# Dual_5V_3_3V_Switch_Mode_PSU.net
KiCad netlist of a schematic drawn in Altium Designer
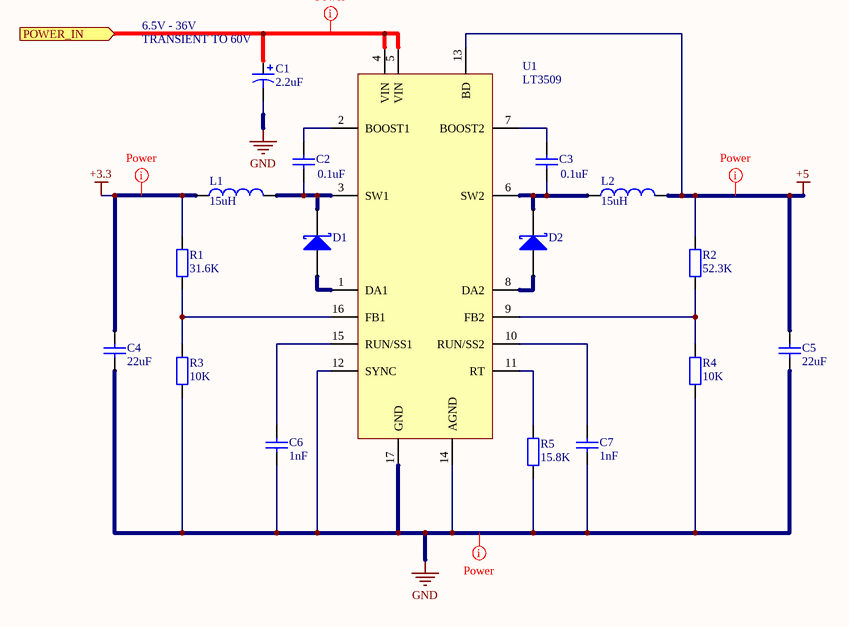
[diagram p0: Dual 5V+3.3V Switch Mode PSU.SchDoc]

(export (version "E")
  (design (tool "Eeschema 10.0.6"))
  (components
    (comp (ref "C1")
      (value "2.2uF")
      (footprint "EEEHC1H2R2R")
      (description "Polarized Capacitor (Radial)")
      (fields (field (name "Comment") "Cap Pol1") (field (name "PUBLISHER") "Altium Limited"))
      (libsource (lib "Miscellaneous Devices") (part "Cap Pol1"))
    )
    (comp (ref "C2")
      (value "0.1uF")
      (footprint "C0603")
      (description "Capacitor")
      (fields (field (name "Comment") "Cap") (field (name "PUBLISHER") "Altium Limited"))
      (libsource (lib "Miscellaneous Devices") (part "Cap"))
    )
    (comp (ref "C3")
      (value "0.1uF")
      (footprint "C0603")
      (description "Capacitor")
      (fields (field (name "Comment") "Cap") (field (name "PUBLISHER") "Altium Limited"))
      (libsource (lib "Miscellaneous Devices") (part "Cap"))
    )
    (comp (ref "C4")
      (value "22uF")
      (footprint "C0805")
      (description "Capacitor")
      (fields (field (name "Comment") "Cap"))
      (libsource (lib "Miscellaneous Devices") (part "Cap"))
    )
    (comp (ref "C5")
      (value "22uF")
      (footprint "C0805")
      (description "Capacitor")
      (fields (field (name "Comment") "Cap"))
      (libsource (lib "Miscellaneous Devices") (part "Cap"))
    )
    (comp (ref "C6")
      (value "1nF")
      (footprint "C0603")
      (description "Capacitor")
      (fields (field (name "Comment") "Cap"))
      (libsource (lib "Miscellaneous Devices") (part "Cap"))
    )
    (comp (ref "C7")
      (value "1nF")
      (footprint "C0603")
      (description "Capacitor")
      (fields (field (name "Comment") "Cap"))
      (libsource (lib "Miscellaneous Devices") (part "Cap"))
    )
    (comp (ref "D1")
      (value "D Schottky")
      (footprint "VS-10BQ030TRPBF")
      (description "Schottky Diode")
      (fields (field (name "PUBLISHER") "Altium Limited"))
      (libsource (lib "Miscellaneous Devices") (part "D Schottky"))
    )
    (comp (ref "D2")
      (value "D Schottky")
      (footprint "VS-10BQ030TRPBF")
      (description "Schottky Diode")
      (fields (field (name "PUBLISHER") "Altium Limited"))
      (libsource (lib "Miscellaneous Devices") (part "D Schottky"))
    )
    (comp (ref "L1")
      (value "15uH")
      (footprint "SDR0604-150YL")
      (description "Inductor")
      (fields (field (name "PUBLISHER") "Altium Limited"))
      (libsource (lib "Miscellaneous Devices") (part "Inductor"))
    )
    (comp (ref "L2")
      (value "15uH")
      (footprint "SDR0604-150YL")
      (description "Inductor")
      (fields (field (name "PUBLISHER") "Altium Limited"))
      (libsource (lib "Miscellaneous Devices") (part "Inductor"))
    )
    (comp (ref "R1")
      (value "31.6K")
      (footprint "R0603")
      (description "Resistor")
      (fields (field (name "Comment") "Res"))
      (libsource (lib "Miscellaneous Devices") (part "Res2"))
    )
    (comp (ref "R2")
      (value "52.3K")
      (footprint "R0603")
      (description "Resistor")
      (fields (field (name "Comment") "Res"))
      (libsource (lib "Miscellaneous Devices") (part "Res2"))
    )
    (comp (ref "R3")
      (value "10K")
      (footprint "R0603")
      (description "Resistor")
      (fields (field (name "Comment") "Res"))
      (libsource (lib "Miscellaneous Devices") (part "Res2"))
    )
    (comp (ref "R4")
      (value "10K")
      (footprint "R0603")
      (description "Resistor")
      (fields (field (name "Comment") "Res"))
      (libsource (lib "Miscellaneous Devices") (part "Res2"))
    )
    (comp (ref "R5")
      (value "15.8K")
      (footprint "R0603")
      (description "Resistor")
      (fields (field (name "Comment") "Res"))
      (libsource (lib "Miscellaneous Devices") (part "Res2"))
    )
    (comp (ref "U1") (value "LT3509") (footprint "LT3509") (libsource (lib "LT3509") (part "LT3509")))
  )
  (nets
    (net (code "1") (name "+3.3") (class "Default")
      (node (ref "C4") (pin "1") (pinfunction "1_1") (pintype "passive"))
      (node (ref "L1") (pin "1") (pinfunction "1_1") (pintype "passive"))
      (node (ref "R1") (pin "2") (pinfunction "2_2") (pintype "passive"))
    )
    (net (code "2") (name "+5") (class "Default")
      (node (ref "C5") (pin "1") (pinfunction "1_1") (pintype "passive"))
      (node (ref "L2") (pin "2") (pinfunction "2_2") (pintype "passive"))
      (node (ref "R2") (pin "2") (pinfunction "2_2") (pintype "passive"))
      (node (ref "U1") (pin "13") (pinfunction "BD_13") (pintype "passive"))
    )
    (net (code "3") (name "/POWER_IN") (class "Default")
      (node (ref "C1") (pin "1") (pinfunction "1_1") (pintype "passive"))
      (node (ref "U1") (pin "4") (pinfunction "VIN_4") (pintype "passive"))
      (node (ref "U1") (pin "5") (pinfunction "VIN_5") (pintype "passive"))
    )
    (net (code "4") (name "GND") (class "Default")
      (node (ref "C1") (pin "2") (pinfunction "2_2") (pintype "passive"))
      (node (ref "C4") (pin "2") (pinfunction "2_2") (pintype "passive"))
      (node (ref "C5") (pin "2") (pinfunction "2_2") (pintype "passive"))
      (node (ref "C6") (pin "2") (pinfunction "2_2") (pintype "passive"))
      (node (ref "C7") (pin "2") (pinfunction "2_2") (pintype "passive"))
      (node (ref "R3") (pin "1") (pinfunction "1_1") (pintype "passive"))
      (node (ref "R4") (pin "1") (pinfunction "1_1") (pintype "passive"))
      (node (ref "R5") (pin "1") (pinfunction "1_1") (pintype "passive"))
      (node (ref "U1") (pin "12") (pinfunction "SYNC_12") (pintype "passive"))
      (node (ref "U1") (pin "14") (pinfunction "AGND_14") (pintype "power_in"))
      (node (ref "U1") (pin "17") (pinfunction "GND_17") (pintype "power_in"))
    )
    (net (code "5") (name "Net-(D1-A)") (class "Default")
      (node (ref "D1") (pin "1") (pinfunction "A_1") (pintype "passive"))
      (node (ref "U1") (pin "1") (pinfunction "DA1_1") (pintype "passive"))
    )
    (net (code "6") (name "Net-(D1-K)") (class "Default")
      (node (ref "C2") (pin "1") (pinfunction "1_1") (pintype "passive"))
      (node (ref "D1") (pin "2") (pinfunction "K_2") (pintype "passive"))
      (node (ref "L1") (pin "2") (pinfunction "2_2") (pintype "passive"))
      (node (ref "U1") (pin "3") (pinfunction "SW1_3") (pintype "passive"))
    )
    (net (code "7") (name "Net-(D2-A)") (class "Default")
      (node (ref "D2") (pin "1") (pinfunction "A_1") (pintype "passive"))
      (node (ref "U1") (pin "8") (pinfunction "DA2_8") (pintype "passive"))
    )
    (net (code "8") (name "Net-(D2-K)") (class "Default")
      (node (ref "C3") (pin "1") (pinfunction "1_1") (pintype "passive"))
      (node (ref "D2") (pin "2") (pinfunction "K_2") (pintype "passive"))
      (node (ref "L2") (pin "1") (pinfunction "1_1") (pintype "passive"))
      (node (ref "U1") (pin "6") (pinfunction "SW2_6") (pintype "passive"))
    )
    (net (code "9") (name "Net-(U1-BOOST1)") (class "Default")
      (node (ref "C2") (pin "2") (pinfunction "2_2") (pintype "passive"))
      (node (ref "U1") (pin "2") (pinfunction "BOOST1_2") (pintype "passive"))
    )
    (net (code "10") (name "Net-(U1-BOOST2)") (class "Default")
      (node (ref "C3") (pin "2") (pinfunction "2_2") (pintype "passive"))
      (node (ref "U1") (pin "7") (pinfunction "BOOST2_7") (pintype "passive"))
    )
    (net (code "11") (name "Net-(U1-FB1)") (class "Default")
      (node (ref "R1") (pin "1") (pinfunction "1_1") (pintype "passive"))
      (node (ref "R3") (pin "2") (pinfunction "2_2") (pintype "passive"))
      (node (ref "U1") (pin "16") (pinfunction "FB1_16") (pintype "passive"))
    )
    (net (code "12") (name "Net-(U1-FB2)") (class "Default")
      (node (ref "R2") (pin "1") (pinfunction "1_1") (pintype "passive"))
      (node (ref "R4") (pin "2") (pinfunction "2_2") (pintype "passive"))
      (node (ref "U1") (pin "9") (pinfunction "FB2_9") (pintype "passive"))
    )
    (net (code "13") (name "Net-(U1-RT)") (class "Default")
      (node (ref "R5") (pin "2") (pinfunction "2_2") (pintype "passive"))
      (node (ref "U1") (pin "11") (pinfunction "RT_11") (pintype "passive"))
    )
    (net (code "14") (name "Net-(U1-RUN{slash}SS1)") (class "Default")
      (node (ref "C6") (pin "1") (pinfunction "1_1") (pintype "passive"))
      (node (ref "U1") (pin "15") (pinfunction "RUN/SS1_15") (pintype "passive"))
    )
    (net (code "15") (name "Net-(U1-RUN{slash}SS2)") (class "Default")
      (node (ref "C7") (pin "1") (pinfunction "1_1") (pintype "passive"))
      (node (ref "U1") (pin "10") (pinfunction "RUN/SS2_10") (pintype "passive"))
    )
  )
)
